# TDA7053A_Stereo.net
KiCad netlist of a schematic drawn in EAGLE
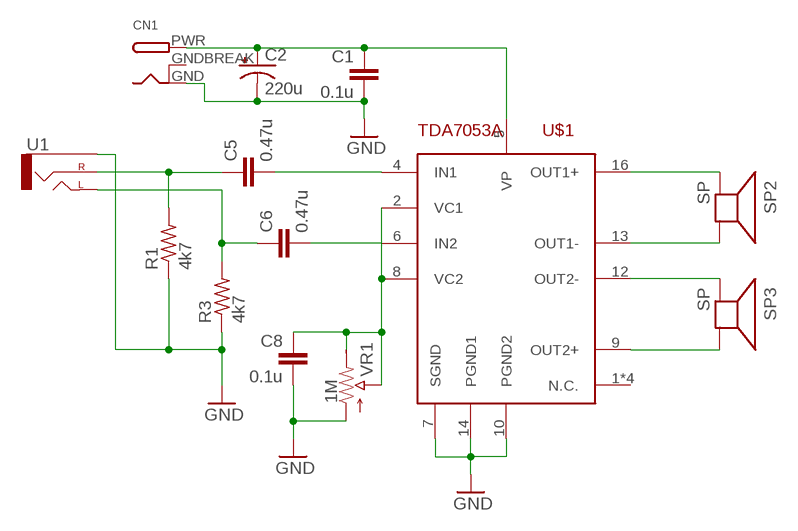
[diagram p0: schematic, sheet 1]

(export (version "E")
  (design (tool "Eeschema 10.0.6"))
  (components
    (comp (ref "C1")
      (value "0.1u")
      (footprint "eagle-import:CAP-PTH-SMALL2")
      (libsource (lib "eagle-import") (part "CAPPTH2"))
    )
    (comp (ref "C2")
      (value "220u")
      (footprint "eagle-import:CPOL-RADIAL-100UF-25V")
      (libsource (lib "eagle-import") (part "CAP_POLPTH1"))
    )
    (comp (ref "C5")
      (value "0.47u")
      (footprint "eagle-import:CAP-PTH-SMALL2")
      (libsource (lib "eagle-import") (part "CAPPTH2"))
    )
    (comp (ref "C6")
      (value "0.47u")
      (footprint "eagle-import:CAP-PTH-SMALL2")
      (libsource (lib "eagle-import") (part "CAPPTH2"))
    )
    (comp (ref "C8")
      (value "0.1u")
      (footprint "eagle-import:CAP-PTH-SMALL2")
      (libsource (lib "eagle-import") (part "CAPPTH2"))
    )
    (comp (ref "CN1")
      (value "DCBARRELPTH")
      (footprint "eagle-import:DCJACK_2MM_PTH")
      (libsource (lib "eagle-import") (part "DCBARRELPTH"))
    )
    (comp (ref "R1")
      (value "4k7")
      (footprint "eagle-import:0204_5")
      (libsource (lib "eagle-import") (part "R-US_0204/5"))
    )
    (comp (ref "R3")
      (value "4k7")
      (footprint "eagle-import:0204_5")
      (libsource (lib "eagle-import") (part "R-US_0204/5"))
    )
    (comp (ref "SP2")
      (value "SP")
      (footprint "eagle-import:PS12")
      (libsource (lib "eagle-import") (part "SP"))
    )
    (comp (ref "SP3")
      (value "SP")
      (footprint "eagle-import:PS12")
      (libsource (lib "eagle-import") (part "SP"))
    )
    (comp (ref "U$1")
      (value "TDA7053A")
      (footprint "eagle-import:DIL16")
      (libsource (lib "eagle-import") (part "TDA7053A"))
    )
    (comp (ref "U1")
      (value "AUDIO-JACKPTH")
      (footprint "eagle-import:AUDIO-JACK")
      (libsource (lib "eagle-import") (part "AUDIO-JACKPTH"))
    )
    (comp (ref "VR1")
      (value "1M")
      (footprint "eagle-import:POT_ALPHA_RV16AF-20")
      (libsource (lib "eagle-import") (part "POT-RV16AF-20"))
    )
  )
  (nets
    (net (code "1") (name "/GNDBREAK") (class "Default")
      (node (ref "CN1") (pin "GNDBREAK") (pinfunction "GNDBREAK_GNDBREAK") (pintype "power_in"))
    )
    (net (code "2") (name "GND") (class "Default")
      (node (ref "C1") (pin "2") (pinfunction "2_2") (pintype "passive"))
      (node (ref "C2") (pin "2") (pinfunction "-_2") (pintype "passive"))
      (node (ref "C8") (pin "2") (pinfunction "2_2") (pintype "passive"))
      (node (ref "CN1") (pin "GND") (pinfunction "GND_GND") (pintype "power_in"))
      (node (ref "R1") (pin "1") (pinfunction "1_1") (pintype "passive"))
      (node (ref "R3") (pin "1") (pinfunction "1_1") (pintype "passive"))
      (node (ref "U$1") (pin "10") (pinfunction "PGND2_10") (pintype "power_in"))
      (node (ref "U$1") (pin "14") (pinfunction "PGND1_14") (pintype "power_in"))
      (node (ref "U$1") (pin "7") (pinfunction "SGND_7") (pintype "power_in"))
      (node (ref "U1") (pin "SLEEVE") (pinfunction "SLEEVE_SLEEVE") (pintype "bidirectional"))
      (node (ref "VR1") (pin "1") (pinfunction "A_1") (pintype "passive"))
    )
    (net (code "3") (name "Net-(C2-+)") (class "Default")
      (node (ref "C1") (pin "1") (pinfunction "1_1") (pintype "passive"))
      (node (ref "C2") (pin "1") (pinfunction "+_1") (pintype "passive"))
      (node (ref "CN1") (pin "PWR") (pinfunction "PWR_PWR") (pintype "power_in"))
      (node (ref "U$1") (pin "5") (pinfunction "VP_5") (pintype "bidirectional"))
    )
    (net (code "4") (name "Net-(SP2-+)") (class "Default")
      (node (ref "SP2") (pin "P$1") (pinfunction "+_P$1") (pintype "passive"))
      (node (ref "U$1") (pin "16") (pinfunction "OUT1+_16") (pintype "output"))
    )
    (net (code "5") (name "Net-(SP2--)") (class "Default")
      (node (ref "SP2") (pin "P$2") (pinfunction "-_P$2") (pintype "passive"))
      (node (ref "U$1") (pin "13") (pinfunction "OUT1-_13") (pintype "output"))
    )
    (net (code "6") (name "Net-(SP3-+)") (class "Default")
      (node (ref "SP3") (pin "P$1") (pinfunction "+_P$1") (pintype "passive"))
      (node (ref "U$1") (pin "12") (pinfunction "OUT2-_12") (pintype "output"))
    )
    (net (code "7") (name "Net-(SP3--)") (class "Default")
      (node (ref "SP3") (pin "P$2") (pinfunction "-_P$2") (pintype "passive"))
      (node (ref "U$1") (pin "9") (pinfunction "OUT2+_9") (pintype "output"))
    )
    (net (code "8") (name "Net-(U$1-IN1)") (class "Default")
      (node (ref "C5") (pin "2") (pinfunction "2_2") (pintype "passive"))
      (node (ref "U$1") (pin "4") (pinfunction "IN1_4") (pintype "input"))
    )
    (net (code "9") (name "Net-(U$1-IN2)") (class "Default")
      (node (ref "C6") (pin "2") (pinfunction "2_2") (pintype "passive"))
      (node (ref "U$1") (pin "6") (pinfunction "IN2_6") (pintype "input"))
    )
    (net (code "10") (name "Net-(U$1-VC1)") (class "Default")
      (node (ref "C8") (pin "1") (pinfunction "1_1") (pintype "passive"))
      (node (ref "U$1") (pin "2") (pinfunction "VC1_2") (pintype "input"))
      (node (ref "U$1") (pin "8") (pinfunction "VC2_8") (pintype "input"))
      (node (ref "VR1") (pin "2") (pinfunction "S_2") (pintype "passive"))
      (node (ref "VR1") (pin "3") (pinfunction "E_3") (pintype "passive"))
    )
    (net (code "11") (name "Net-(U1-LEFT)") (class "Default")
      (node (ref "C6") (pin "1") (pinfunction "1_1") (pintype "passive"))
      (node (ref "R3") (pin "2") (pinfunction "2_2") (pintype "passive"))
      (node (ref "U1") (pin "TIP") (pinfunction "LEFT_TIP") (pintype "bidirectional"))
    )
    (net (code "12") (name "Net-(U1-RIGHT)") (class "Default")
      (node (ref "C5") (pin "1") (pinfunction "1_1") (pintype "passive"))
      (node (ref "R1") (pin "2") (pinfunction "2_2") (pintype "passive"))
      (node (ref "U1") (pin "RING") (pinfunction "RIGHT_RING") (pintype "bidirectional"))
    )
    (net (code "13") (name "unconnected-(U$1-N.C.-Pad1)") (class "Default")
      (node (ref "U$1") (pin "1") (pinfunction "N.C._1") (pintype "no_connect"))
    )
    (net (code "14") (name "unconnected-(U$1-N.C.-Pad3)") (class "Default")
      (node (ref "U$1") (pin "3") (pinfunction "N.C._3") (pintype "no_connect"))
    )
    (net (code "15") (name "unconnected-(U$1-N.C.-Pad11)") (class "Default")
      (node (ref "U$1") (pin "11") (pinfunction "N.C._11") (pintype "no_connect"))
    )
    (net (code "16") (name "unconnected-(U$1-N.C.-Pad15)") (class "Default")
      (node (ref "U$1") (pin "15") (pinfunction "N.C._15") (pintype "no_connect"))
    )
  )
)
